# PiTopUSBHub.net
KiCad netlist of a schematic drawn in Altium Designer
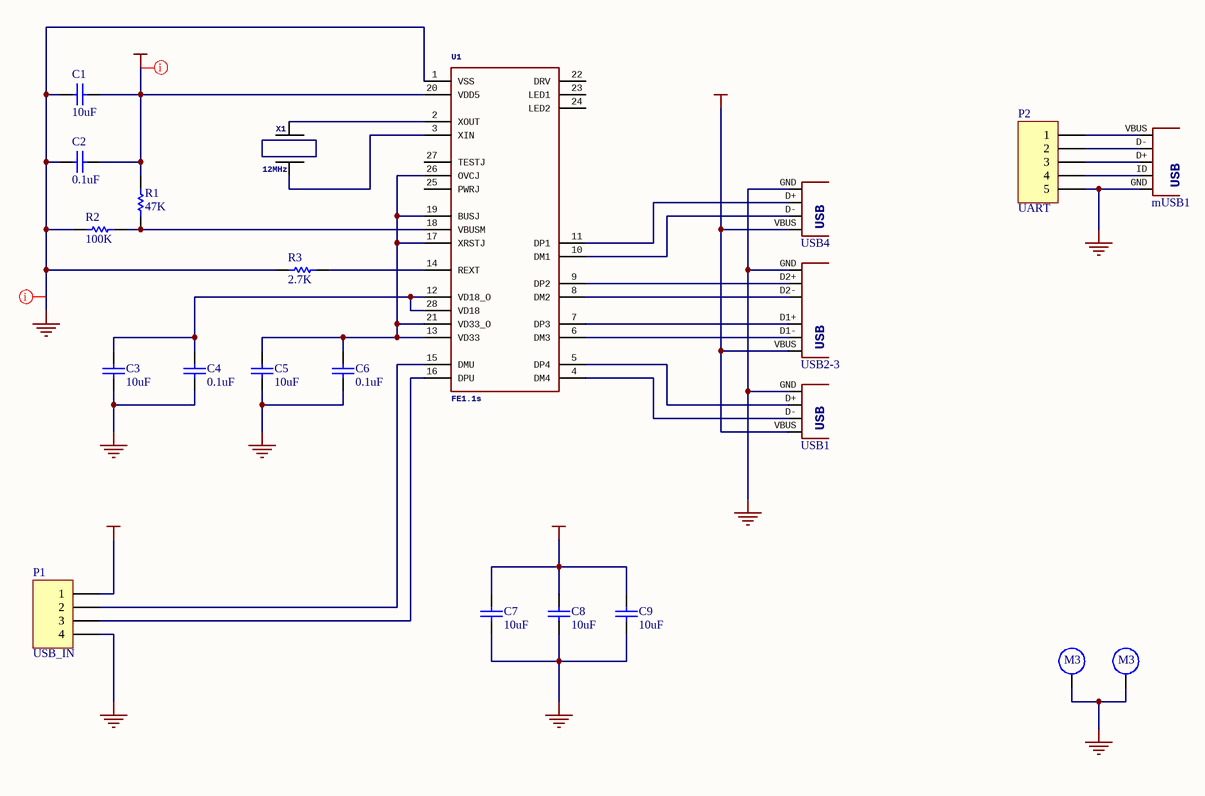
[diagram p0: PiTopUSBHub.SchDoc]

(export (version "E")
  (design (tool "Eeschema 10.0.6"))
  (components
    (comp (ref "C1")
      (value "10uF")
      (footprint "C0805")
      (description "Ceramic Chip Capacitor - Standard")
      (fields (field (name "Comment") "C0805") (field (name "PUBLISHER") "Altium Limited"))
      (libsource (lib "KEMET Chip Capacitor") (part "C0805"))
    )
    (comp (ref "C2")
      (value "0.1uF")
      (footprint "C0805")
      (description "Ceramic Chip Capacitor - Standard")
      (fields (field (name "Comment") "C0805") (field (name "PUBLISHER") "Altium Limited"))
      (libsource (lib "KEMET Chip Capacitor") (part "C0805"))
    )
    (comp (ref "C3")
      (value "10uF")
      (footprint "C0805")
      (description "Ceramic Chip Capacitor - Standard")
      (fields (field (name "Comment") "C0805") (field (name "PUBLISHER") "Altium Limited"))
      (libsource (lib "KEMET Chip Capacitor") (part "C0805"))
    )
    (comp (ref "C4")
      (value "0.1uF")
      (footprint "C0805")
      (description "Ceramic Chip Capacitor - Standard")
      (fields (field (name "Comment") "C0805") (field (name "PUBLISHER") "Altium Limited"))
      (libsource (lib "KEMET Chip Capacitor") (part "C0805"))
    )
    (comp (ref "C5")
      (value "10uF")
      (footprint "C0805")
      (description "Ceramic Chip Capacitor - Standard")
      (fields (field (name "Comment") "C0805") (field (name "PUBLISHER") "Altium Limited"))
      (libsource (lib "KEMET Chip Capacitor") (part "C0805"))
    )
    (comp (ref "C6")
      (value "0.1uF")
      (footprint "C0805")
      (description "Ceramic Chip Capacitor - Standard")
      (fields (field (name "Comment") "C0805") (field (name "PUBLISHER") "Altium Limited"))
      (libsource (lib "KEMET Chip Capacitor") (part "C0805"))
    )
    (comp (ref "C7")
      (value "10uF")
      (footprint "C0805")
      (description "Ceramic Chip Capacitor - Standard")
      (fields (field (name "Comment") "C0805") (field (name "PUBLISHER") "Altium Limited"))
      (libsource (lib "KEMET Chip Capacitor") (part "C0805"))
    )
    (comp (ref "C8")
      (value "10uF")
      (footprint "C0805")
      (description "Ceramic Chip Capacitor - Standard")
      (fields (field (name "Comment") "C0805") (field (name "PUBLISHER") "Altium Limited"))
      (libsource (lib "KEMET Chip Capacitor") (part "C0805"))
    )
    (comp (ref "C9")
      (value "10uF")
      (footprint "C0805")
      (description "Ceramic Chip Capacitor - Standard")
      (fields (field (name "Comment") "C0805") (field (name "PUBLISHER") "Altium Limited"))
      (libsource (lib "KEMET Chip Capacitor") (part "C0805"))
    )
    (comp (ref "H1") (value "M3") (footprint "M3") (libsource (lib "lib") (part "M3")))
    (comp (ref "H2") (value "M3") (footprint "M3") (libsource (lib "lib") (part "M3")))
    (comp (ref "mUSB1")
      (value "miniUSB-PTH")
      (footprint "miniUSB-F-PTH")
      (fields (field (name "USB") "USB"))
      (libsource (lib "lib") (part "miniUSBA-PTH"))
    )
    (comp (ref "P1")
      (value "USB_IN")
      (footprint "HDR1X4")
      (description "Header, 4-Pin")
      (fields (field (name "PUBLISHER") "Altium Limited"))
      (libsource (lib "Miscellaneous Connectors") (part "Header 4"))
    )
    (comp (ref "P2")
      (value "UART")
      (footprint "HDR1X5")
      (description "Header, 5-Pin")
      (fields (field (name "PUBLISHER") "Altium Limited"))
      (libsource (lib "Miscellaneous Connectors") (part "Header 5"))
    )
    (comp (ref "R1")
      (value "47K")
      (footprint "R0805")
      (fields (field (name "PUBLISHER") "Altium Limited"))
      (libsource (lib "lib") (part "R0805"))
    )
    (comp (ref "R2")
      (value "100K")
      (footprint "R0805")
      (fields (field (name "PUBLISHER") "Altium Limited"))
      (libsource (lib "lib") (part "R0805"))
    )
    (comp (ref "R3")
      (value "2.7K")
      (footprint "R0805")
      (fields (field (name "PUBLISHER") "Altium Limited"))
      (libsource (lib "lib") (part "R0805"))
    )
    (comp (ref "U1")
      (value "FE1.1S")
      (footprint "FE1.1S_SSOP-28")
      (fields (field (name "FE1.1S") "FE1.1s"))
      (libsource (lib "lib") (part "FE1.1S"))
    )
    (comp (ref "USB1")
      (value "USBA-PTH")
      (footprint "USB-A-F-PTH")
      (fields (field (name "USB") "USB"))
      (libsource (lib "lib") (part "USBA-PTH"))
    )
    (comp (ref "USB2-3")
      (value "USBA2x-PTH")
      (footprint "USB-A-2x-F-PTH")
      (fields (field (name "USB") "USB"))
      (libsource (lib "lib") (part "USBA2x-PTH"))
    )
    (comp (ref "USB4")
      (value "USBA-PTH")
      (footprint "USB-A-F-PTH")
      (fields (field (name "USB") "USB"))
      (libsource (lib "lib") (part "USBA-PTH"))
    )
    (comp (ref "X1")
      (value "12MHz")
      (footprint "XTAL_G5032")
      (description "PTH: ...   SMD: ...   Cylinder: CMR200T-32.768KDZBT")
      (libsource (lib "lib") (part "CRYSTALHC49UP"))
    )
  )
  (nets
    (net (code "1") (name "GND") (class "Default")
      (node (ref "C1") (pin "2") (pinfunction "2_2") (pintype "passive"))
      (node (ref "C2") (pin "2") (pinfunction "2_2") (pintype "passive"))
      (node (ref "C3") (pin "2") (pinfunction "2_2") (pintype "passive"))
      (node (ref "C4") (pin "2") (pinfunction "2_2") (pintype "passive"))
      (node (ref "C5") (pin "2") (pinfunction "2_2") (pintype "passive"))
      (node (ref "C6") (pin "2") (pinfunction "2_2") (pintype "passive"))
      (node (ref "C7") (pin "2") (pinfunction "2_2") (pintype "passive"))
      (node (ref "C8") (pin "2") (pinfunction "2_2") (pintype "passive"))
      (node (ref "C9") (pin "2") (pinfunction "2_2") (pintype "passive"))
      (node (ref "H1") (pin "1") (pinfunction "1_1") (pintype "passive"))
      (node (ref "H2") (pin "1") (pinfunction "1_1") (pintype "passive"))
      (node (ref "P1") (pin "4") (pinfunction "4_4") (pintype "passive"))
      (node (ref "P2") (pin "5") (pinfunction "5_5") (pintype "passive"))
      (node (ref "R2") (pin "2") (pinfunction "2_2") (pintype "passive"))
      (node (ref "R3") (pin "1") (pinfunction "1_1") (pintype "passive"))
      (node (ref "U1") (pin "1") (pinfunction "VSS_1") (pintype "passive"))
      (node (ref "USB1") (pin "GND") (pinfunction "GND_GND") (pintype "passive"))
      (node (ref "USB2-3") (pin "GND") (pinfunction "GND_GND") (pintype "passive"))
      (node (ref "USB4") (pin "GND") (pinfunction "GND_GND") (pintype "passive"))
      (node (ref "mUSB1") (pin "GND") (pinfunction "GND_GND") (pintype "passive"))
    )
    (net (code "2") (name "Net-(P2-Pad1)") (class "Default")
      (node (ref "P2") (pin "1") (pinfunction "1_1") (pintype "passive"))
      (node (ref "mUSB1") (pin "VBUS") (pinfunction "VBUS_VBUS") (pintype "passive"))
    )
    (net (code "3") (name "Net-(P2-Pad2)") (class "Default")
      (node (ref "P2") (pin "2") (pinfunction "2_2") (pintype "passive"))
      (node (ref "mUSB1") (pin "D-") (pinfunction "D-_D-") (pintype "passive"))
    )
    (net (code "4") (name "Net-(P2-Pad3)") (class "Default")
      (node (ref "P2") (pin "3") (pinfunction "3_3") (pintype "passive"))
      (node (ref "mUSB1") (pin "D+") (pinfunction "D+_D+") (pintype "passive"))
    )
    (net (code "5") (name "Net-(P2-Pad4)") (class "Default")
      (node (ref "P2") (pin "4") (pinfunction "4_4") (pintype "passive"))
      (node (ref "mUSB1") (pin "ID") (pinfunction "ID_ID") (pintype "passive"))
    )
    (net (code "6") (name "Net-(U1-BUSJ)") (class "Default")
      (node (ref "C5") (pin "1") (pinfunction "1_1") (pintype "passive"))
      (node (ref "C6") (pin "1") (pinfunction "1_1") (pintype "passive"))
      (node (ref "U1") (pin "13") (pinfunction "VD33_13") (pintype "passive"))
      (node (ref "U1") (pin "17") (pinfunction "XRSTJ_17") (pintype "passive"))
      (node (ref "U1") (pin "19") (pinfunction "BUSJ_19") (pintype "passive"))
      (node (ref "U1") (pin "21") (pinfunction "VD33_O_21") (pintype "passive"))
      (node (ref "U1") (pin "26") (pinfunction "OVCJ_26") (pintype "passive"))
    )
    (net (code "7") (name "Net-(U1-DM1)") (class "Default")
      (node (ref "U1") (pin "10") (pinfunction "DM1_10") (pintype "passive"))
      (node (ref "USB4") (pin "D-") (pinfunction "D-_D-") (pintype "passive"))
    )
    (net (code "8") (name "Net-(U1-DM2)") (class "Default")
      (node (ref "U1") (pin "8") (pinfunction "DM2_8") (pintype "passive"))
      (node (ref "USB2-3") (pin "D2-") (pinfunction "D2-_D2-") (pintype "passive"))
    )
    (net (code "9") (name "Net-(U1-DM3)") (class "Default")
      (node (ref "U1") (pin "6") (pinfunction "DM3_6") (pintype "passive"))
      (node (ref "USB2-3") (pin "D1-") (pinfunction "D1-_D1-") (pintype "passive"))
    )
    (net (code "10") (name "Net-(U1-DM4)") (class "Default")
      (node (ref "U1") (pin "4") (pinfunction "DM4_4") (pintype "passive"))
      (node (ref "USB1") (pin "D-") (pinfunction "D-_D-") (pintype "passive"))
    )
    (net (code "11") (name "Net-(U1-DMU)") (class "Default")
      (node (ref "P1") (pin "2") (pinfunction "2_2") (pintype "passive"))
      (node (ref "U1") (pin "15") (pinfunction "DMU_15") (pintype "passive"))
    )
    (net (code "12") (name "Net-(U1-DP1)") (class "Default")
      (node (ref "U1") (pin "11") (pinfunction "DP1_11") (pintype "passive"))
      (node (ref "USB4") (pin "D+") (pinfunction "D+_D+") (pintype "passive"))
    )
    (net (code "13") (name "Net-(U1-DP2)") (class "Default")
      (node (ref "U1") (pin "9") (pinfunction "DP2_9") (pintype "passive"))
      (node (ref "USB2-3") (pin "D2+") (pinfunction "D2+_D2+") (pintype "passive"))
    )
    (net (code "14") (name "Net-(U1-DP3)") (class "Default")
      (node (ref "U1") (pin "7") (pinfunction "DP3_7") (pintype "passive"))
      (node (ref "USB2-3") (pin "D1+") (pinfunction "D1+_D1+") (pintype "passive"))
    )
    (net (code "15") (name "Net-(U1-DP4)") (class "Default")
      (node (ref "U1") (pin "5") (pinfunction "DP4_5") (pintype "passive"))
      (node (ref "USB1") (pin "D+") (pinfunction "D+_D+") (pintype "passive"))
    )
    (net (code "16") (name "Net-(U1-DPU)") (class "Default")
      (node (ref "P1") (pin "3") (pinfunction "3_3") (pintype "passive"))
      (node (ref "U1") (pin "16") (pinfunction "DPU_16") (pintype "passive"))
    )
    (net (code "17") (name "Net-(U1-REXT)") (class "Default")
      (node (ref "R3") (pin "2") (pinfunction "2_2") (pintype "passive"))
      (node (ref "U1") (pin "14") (pinfunction "REXT_14") (pintype "passive"))
    )
    (net (code "18") (name "Net-(U1-VBUSM)") (class "Default")
      (node (ref "R1") (pin "2") (pinfunction "2_2") (pintype "passive"))
      (node (ref "R2") (pin "1") (pinfunction "1_1") (pintype "passive"))
      (node (ref "U1") (pin "18") (pinfunction "VBUSM_18") (pintype "passive"))
    )
    (net (code "19") (name "Net-(U1-VD18)") (class "Default")
      (node (ref "C3") (pin "1") (pinfunction "1_1") (pintype "passive"))
      (node (ref "C4") (pin "1") (pinfunction "1_1") (pintype "passive"))
      (node (ref "U1") (pin "12") (pinfunction "VD18_O_12") (pintype "passive"))
      (node (ref "U1") (pin "28") (pinfunction "VD18_28") (pintype "passive"))
    )
    (net (code "20") (name "Net-(U1-XIN)") (class "Default")
      (node (ref "U1") (pin "3") (pinfunction "XIN_3") (pintype "passive"))
      (node (ref "X1") (pin "1") (pinfunction "1_1") (pintype "passive"))
    )
    (net (code "21") (name "Net-(U1-XOUT)") (class "Default")
      (node (ref "U1") (pin "2") (pinfunction "XOUT_2") (pintype "passive"))
      (node (ref "X1") (pin "2") (pinfunction "2_2") (pintype "passive"))
    )
    (net (code "22") (name "VCC") (class "Default")
      (node (ref "C1") (pin "1") (pinfunction "1_1") (pintype "passive"))
      (node (ref "C2") (pin "1") (pinfunction "1_1") (pintype "passive"))
      (node (ref "C7") (pin "1") (pinfunction "1_1") (pintype "passive"))
      (node (ref "C8") (pin "1") (pinfunction "1_1") (pintype "passive"))
      (node (ref "C9") (pin "1") (pinfunction "1_1") (pintype "passive"))
      (node (ref "P1") (pin "1") (pinfunction "1_1") (pintype "passive"))
      (node (ref "R1") (pin "1") (pinfunction "1_1") (pintype "passive"))
      (node (ref "U1") (pin "20") (pinfunction "VDD5_20") (pintype "passive"))
      (node (ref "USB1") (pin "VBUS") (pinfunction "VBUS_VBUS") (pintype "passive"))
      (node (ref "USB2-3") (pin "VBUS") (pinfunction "VBUS_VBUS") (pintype "passive"))
      (node (ref "USB4") (pin "VBUS") (pinfunction "VBUS_VBUS") (pintype "passive"))
    )
    (net (code "23") (name "unconnected-(U1-DRV-Pad22)") (class "Default")
      (node (ref "U1") (pin "22") (pinfunction "DRV_22") (pintype "passive"))
    )
    (net (code "24") (name "unconnected-(U1-LED1-Pad23)") (class "Default")
      (node (ref "U1") (pin "23") (pinfunction "LED1_23") (pintype "passive"))
    )
    (net (code "25") (name "unconnected-(U1-LED2-Pad24)") (class "Default")
      (node (ref "U1") (pin "24") (pinfunction "LED2_24") (pintype "passive"))
    )
    (net (code "26") (name "unconnected-(U1-PWRJ-Pad25)") (class "Default")
      (node (ref "U1") (pin "25") (pinfunction "PWRJ_25") (pintype "passive"))
    )
    (net (code "27") (name "unconnected-(U1-TESTJ-Pad27)") (class "Default")
      (node (ref "U1") (pin "27") (pinfunction "TESTJ_27") (pintype "passive"))
    )
  )
)
